# 02_LemonAutopilot_2.net
KiCad netlist of a schematic drawn in Altium Designer
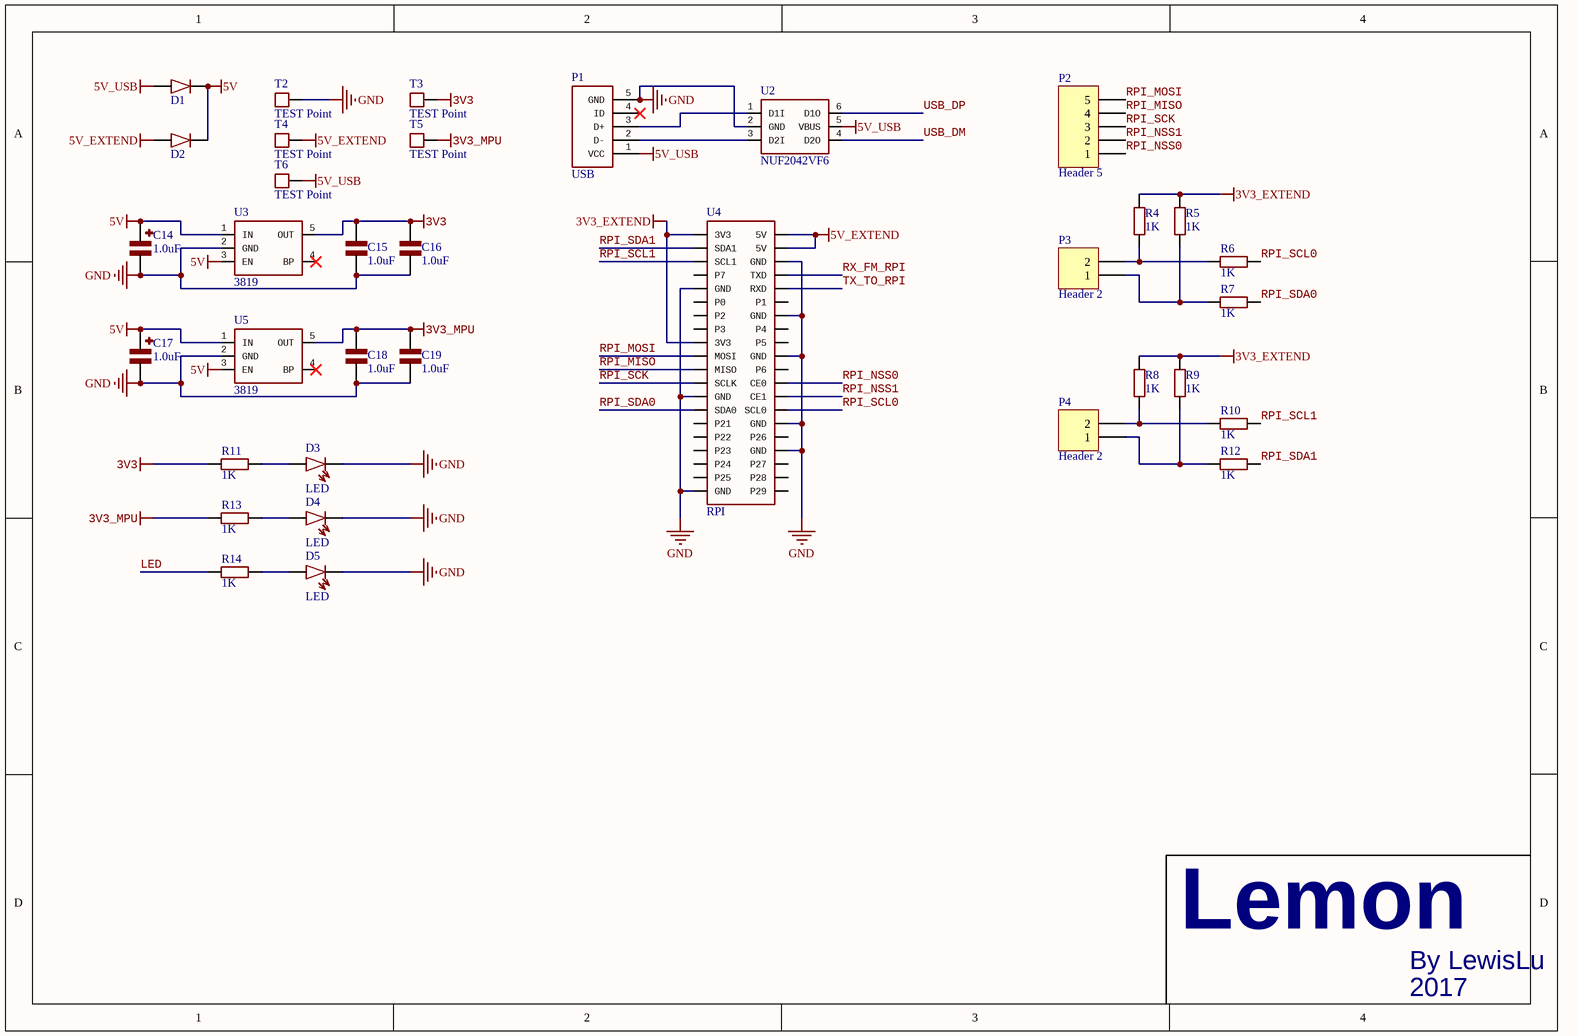
[diagram p0: 02.LemonAutopilot_2.SchDoc]

(export (version "E")
  (design (tool "Eeschema 10.0.6"))
  (components
    (comp (ref "C14") (value "1.0uF") (footprint "3216_C") (libsource (lib "Library") (part "C3216")))
    (comp (ref "C15") (value "1.0uF") (footprint "0603_C") (libsource (lib "Library") (part "C0603")))
    (comp (ref "C16") (value "1.0uF") (footprint "0603_C") (libsource (lib "Library") (part "C0603")))
    (comp (ref "C17") (value "1.0uF") (footprint "3216_C") (libsource (lib "Library") (part "C3216")))
    (comp (ref "C18") (value "1.0uF") (footprint "0603_C") (libsource (lib "Library") (part "C0603")))
    (comp (ref "C19") (value "1.0uF") (footprint "0603_C") (libsource (lib "Library") (part "C0603")))
    (comp (ref "D1") (value "D") (footprint "SOD-323") (libsource (lib "Library") (part "D0603")))
    (comp (ref "D2") (value "D") (footprint "SOD-323") (libsource (lib "Library") (part "D0603")))
    (comp (ref "D3") (value "LED") (footprint "0603_D") (libsource (lib "Library") (part "D0603_LED")))
    (comp (ref "D4") (value "LED") (footprint "0603_D") (libsource (lib "Library") (part "D0603_LED")))
    (comp (ref "D5") (value "LED") (footprint "0603_D") (libsource (lib "Library") (part "D0603_LED")))
    (comp (ref "P1") (value "USB") (footprint "MICROUSB") (libsource (lib "Library") (part "USB")))
    (comp (ref "P2")
      (value "Header 5")
      (footprint "HDR1X5")
      (description "Header, 5-Pin")
      (fields (field (name "PUBLISHER") "Altium Limited"))
      (libsource (lib "Miscellaneous Connectors") (part "Header 5"))
    )
    (comp (ref "P3")
      (value "Header 2")
      (footprint "HDR1X2")
      (description "Header, 2-Pin")
      (fields (field (name "PUBLISHER") "Altium Limited"))
      (libsource (lib "Miscellaneous Connectors") (part "Header 2"))
    )
    (comp (ref "P4")
      (value "Header 2")
      (footprint "HDR1X2")
      (description "Header, 2-Pin")
      (fields (field (name "PUBLISHER") "Altium Limited"))
      (libsource (lib "Miscellaneous Connectors") (part "Header 2"))
    )
    (comp (ref "R4") (value "1K") (footprint "0603_R") (libsource (lib "Library") (part "R0603")))
    (comp (ref "R5") (value "1K") (footprint "0603_R") (libsource (lib "Library") (part "R0603")))
    (comp (ref "R6") (value "1K") (footprint "0603_R") (libsource (lib "") (part "R0603_1")))
    (comp (ref "R7") (value "1K") (footprint "0603_R") (libsource (lib "") (part "R0603_1")))
    (comp (ref "R8") (value "1K") (footprint "0603_R") (libsource (lib "Library") (part "R0603")))
    (comp (ref "R9") (value "1K") (footprint "0603_R") (libsource (lib "Library") (part "R0603")))
    (comp (ref "R10") (value "1K") (footprint "0603_R") (libsource (lib "") (part "R0603_1")))
    (comp (ref "R11") (value "1K") (footprint "0603_R") (libsource (lib "") (part "R0603_1")))
    (comp (ref "R12") (value "1K") (footprint "0603_R") (libsource (lib "") (part "R0603_1")))
    (comp (ref "R13") (value "1K") (footprint "0603_R") (libsource (lib "") (part "R0603_1")))
    (comp (ref "R14") (value "1K") (footprint "0603_R") (libsource (lib "") (part "R0603_1")))
    (comp (ref "T2") (value "TEST Point") (footprint "TEST") (libsource (lib "Library") (part "TEST")))
    (comp (ref "T3") (value "TEST Point") (footprint "TEST") (libsource (lib "Library") (part "TEST")))
    (comp (ref "T4") (value "TEST Point") (footprint "TEST") (libsource (lib "Library") (part "TEST")))
    (comp (ref "T5") (value "TEST Point") (footprint "TEST") (libsource (lib "Library") (part "TEST")))
    (comp (ref "T6") (value "TEST Point") (footprint "TEST") (libsource (lib "Library") (part "TEST")))
    (comp (ref "U2") (value "NUF2042VF6") (libsource (lib "Library") (part "NUF2042XV6")))
    (comp (ref "U3") (value "3819") (footprint "SOT23-5") (libsource (lib "Library") (part "SPX3819")))
    (comp (ref "U4") (value "RPI") (libsource (lib "Library") (part "RPI_EXTEND")))
    (comp (ref "U5") (value "3819") (footprint "SOT23-5") (libsource (lib "Library") (part "SPX3819")))
  )
  (nets
    (net (code "1") (name "/LED") (class "Default")
      (node (ref "R14") (pin "1") (pinfunction "1_1") (pintype "passive"))
    )
    (net (code "2") (name "/RPI_MISO") (class "Default")
      (node (ref "P2") (pin "4") (pinfunction "4_4") (pintype "passive"))
      (node (ref "U4") (pin "21") (pinfunction "MISO_21") (pintype "passive"))
    )
    (net (code "3") (name "/RPI_MOSI") (class "Default")
      (node (ref "P2") (pin "5") (pinfunction "5_5") (pintype "passive"))
      (node (ref "U4") (pin "19") (pinfunction "MOSI_19") (pintype "passive"))
    )
    (net (code "4") (name "/RPI_NSS0") (class "Default")
      (node (ref "P2") (pin "1") (pinfunction "1_1") (pintype "passive"))
      (node (ref "U4") (pin "24") (pinfunction "CE0_24") (pintype "passive"))
    )
    (net (code "5") (name "/RPI_NSS1") (class "Default")
      (node (ref "P2") (pin "2") (pinfunction "2_2") (pintype "passive"))
      (node (ref "U4") (pin "26") (pinfunction "CE1_26") (pintype "passive"))
    )
    (net (code "6") (name "/RPI_SCK") (class "Default")
      (node (ref "P2") (pin "3") (pinfunction "3_3") (pintype "passive"))
      (node (ref "U4") (pin "23") (pinfunction "SCLK_23") (pintype "passive"))
    )
    (net (code "7") (name "/RPI_SCL0") (class "Default")
      (node (ref "R6") (pin "2") (pinfunction "2_2") (pintype "passive"))
      (node (ref "U4") (pin "28") (pinfunction "SCL0_28") (pintype "passive"))
    )
    (net (code "8") (name "/RPI_SCL1") (class "Default")
      (node (ref "R10") (pin "2") (pinfunction "2_2") (pintype "passive"))
      (node (ref "U4") (pin "5") (pinfunction "SCL1_5") (pintype "passive"))
    )
    (net (code "9") (name "/RPI_SDA0") (class "Default")
      (node (ref "R7") (pin "2") (pinfunction "2_2") (pintype "passive"))
      (node (ref "U4") (pin "27") (pinfunction "SDA0_27") (pintype "passive"))
    )
    (net (code "10") (name "/RPI_SDA1") (class "Default")
      (node (ref "R12") (pin "2") (pinfunction "2_2") (pintype "passive"))
      (node (ref "U4") (pin "3") (pinfunction "SDA1_3") (pintype "passive"))
    )
    (net (code "11") (name "/RX_FM_RPI") (class "Default")
      (node (ref "U4") (pin "8") (pinfunction "TXD_8") (pintype "passive"))
    )
    (net (code "12") (name "/TX_TO_RPI") (class "Default")
      (node (ref "U4") (pin "10") (pinfunction "RXD_10") (pintype "passive"))
    )
    (net (code "13") (name "/USB_DM") (class "Default")
      (node (ref "U2") (pin "4") (pinfunction "D2O_4") (pintype "passive"))
    )
    (net (code "14") (name "/USB_DP") (class "Default")
      (node (ref "U2") (pin "6") (pinfunction "D1O_6") (pintype "passive"))
    )
    (net (code "15") (name "3V3") (class "Default")
      (node (ref "C15") (pin "2") (pinfunction "2_2") (pintype "passive"))
      (node (ref "C16") (pin "2") (pinfunction "2_2") (pintype "passive"))
      (node (ref "R11") (pin "1") (pinfunction "1_1") (pintype "passive"))
      (node (ref "T3") (pin "0") (pinfunction "TEST_0") (pintype "passive"))
      (node (ref "U3") (pin "5") (pinfunction "OUT_5") (pintype "passive"))
    )
    (net (code "16") (name "3V3_EXTEND") (class "Default")
      (node (ref "R4") (pin "1") (pinfunction "1_1") (pintype "passive"))
      (node (ref "R5") (pin "1") (pinfunction "1_1") (pintype "passive"))
      (node (ref "R8") (pin "1") (pinfunction "1_1") (pintype "passive"))
      (node (ref "R9") (pin "1") (pinfunction "1_1") (pintype "passive"))
      (node (ref "U4") (pin "1") (pinfunction "3V3_1") (pintype "passive"))
      (node (ref "U4") (pin "17") (pinfunction "3V3_17") (pintype "passive"))
    )
    (net (code "17") (name "3V3_MPU") (class "Default")
      (node (ref "C18") (pin "2") (pinfunction "2_2") (pintype "passive"))
      (node (ref "C19") (pin "2") (pinfunction "2_2") (pintype "passive"))
      (node (ref "R13") (pin "1") (pinfunction "1_1") (pintype "passive"))
      (node (ref "T5") (pin "0") (pinfunction "TEST_0") (pintype "passive"))
      (node (ref "U5") (pin "5") (pinfunction "OUT_5") (pintype "passive"))
    )
    (net (code "18") (name "5V") (class "Default")
      (node (ref "C14") (pin "1") (pinfunction "1_1") (pintype "passive"))
      (node (ref "C17") (pin "1") (pinfunction "1_1") (pintype "passive"))
      (node (ref "D1") (pin "2") (pinfunction "2_2") (pintype "passive"))
      (node (ref "D2") (pin "2") (pinfunction "2_2") (pintype "passive"))
      (node (ref "U3") (pin "1") (pinfunction "IN_1") (pintype "passive"))
      (node (ref "U3") (pin "3") (pinfunction "EN_3") (pintype "passive"))
      (node (ref "U5") (pin "1") (pinfunction "IN_1") (pintype "passive"))
      (node (ref "U5") (pin "3") (pinfunction "EN_3") (pintype "passive"))
    )
    (net (code "19") (name "5V_EXTEND") (class "Default")
      (node (ref "D2") (pin "1") (pinfunction "1_1") (pintype "passive"))
      (node (ref "T4") (pin "0") (pinfunction "TEST_0") (pintype "passive"))
      (node (ref "U4") (pin "2") (pinfunction "5V_2") (pintype "passive"))
      (node (ref "U4") (pin "4") (pinfunction "5V_4") (pintype "passive"))
    )
    (net (code "20") (name "5V_USB") (class "Default")
      (node (ref "D1") (pin "1") (pinfunction "1_1") (pintype "passive"))
      (node (ref "P1") (pin "1") (pinfunction "VCC_1") (pintype "passive"))
      (node (ref "T6") (pin "0") (pinfunction "TEST_0") (pintype "passive"))
      (node (ref "U2") (pin "5") (pinfunction "VBUS_5") (pintype "passive"))
    )
    (net (code "21") (name "GND") (class "Default")
      (node (ref "C14") (pin "2") (pinfunction "2_2") (pintype "passive"))
      (node (ref "C15") (pin "1") (pinfunction "1_1") (pintype "passive"))
      (node (ref "C16") (pin "1") (pinfunction "1_1") (pintype "passive"))
      (node (ref "C17") (pin "2") (pinfunction "2_2") (pintype "passive"))
      (node (ref "C18") (pin "1") (pinfunction "1_1") (pintype "passive"))
      (node (ref "C19") (pin "1") (pinfunction "1_1") (pintype "passive"))
      (node (ref "D3") (pin "2") (pinfunction "2_2") (pintype "passive"))
      (node (ref "D4") (pin "2") (pinfunction "2_2") (pintype "passive"))
      (node (ref "D5") (pin "2") (pinfunction "2_2") (pintype "passive"))
      (node (ref "P1") (pin "5") (pinfunction "GND_5") (pintype "passive"))
      (node (ref "T2") (pin "0") (pinfunction "TEST_0") (pintype "passive"))
      (node (ref "U2") (pin "2") (pinfunction "GND_2") (pintype "passive"))
      (node (ref "U3") (pin "2") (pinfunction "GND_2") (pintype "passive"))
      (node (ref "U4") (pin "14") (pinfunction "GND_14") (pintype "passive"))
      (node (ref "U4") (pin "20") (pinfunction "GND_20") (pintype "passive"))
      (node (ref "U4") (pin "25") (pinfunction "GND_25") (pintype "passive"))
      (node (ref "U4") (pin "30") (pinfunction "GND_30") (pintype "passive"))
      (node (ref "U4") (pin "34") (pinfunction "GND_34") (pintype "passive"))
      (node (ref "U4") (pin "39") (pinfunction "GND_39") (pintype "passive"))
      (node (ref "U4") (pin "6") (pinfunction "GND_6") (pintype "passive"))
      (node (ref "U4") (pin "9") (pinfunction "GND_9") (pintype "passive"))
      (node (ref "U5") (pin "2") (pinfunction "GND_2") (pintype "passive"))
    )
    (net (code "22") (name "Net-(D3-Pad1)") (class "Default")
      (node (ref "D3") (pin "1") (pinfunction "1_1") (pintype "passive"))
      (node (ref "R11") (pin "2") (pinfunction "2_2") (pintype "passive"))
    )
    (net (code "23") (name "Net-(D4-Pad1)") (class "Default")
      (node (ref "D4") (pin "1") (pinfunction "1_1") (pintype "passive"))
      (node (ref "R13") (pin "2") (pinfunction "2_2") (pintype "passive"))
    )
    (net (code "24") (name "Net-(D5-Pad1)") (class "Default")
      (node (ref "D5") (pin "1") (pinfunction "1_1") (pintype "passive"))
      (node (ref "R14") (pin "2") (pinfunction "2_2") (pintype "passive"))
    )
    (net (code "25") (name "Net-(P1-D+)") (class "Default")
      (node (ref "P1") (pin "3") (pinfunction "D+_3") (pintype "passive"))
      (node (ref "U2") (pin "1") (pinfunction "D1I_1") (pintype "passive"))
    )
    (net (code "26") (name "Net-(P1-D-)") (class "Default")
      (node (ref "P1") (pin "2") (pinfunction "D-_2") (pintype "passive"))
      (node (ref "U2") (pin "3") (pinfunction "D2I_3") (pintype "passive"))
    )
    (net (code "27") (name "Net-(P3-Pad1)") (class "Default")
      (node (ref "P3") (pin "1") (pinfunction "1_1") (pintype "passive"))
      (node (ref "R5") (pin "2") (pinfunction "2_2") (pintype "passive"))
      (node (ref "R7") (pin "1") (pinfunction "1_1") (pintype "passive"))
    )
    (net (code "28") (name "Net-(P3-Pad2)") (class "Default")
      (node (ref "P3") (pin "2") (pinfunction "2_2") (pintype "passive"))
      (node (ref "R4") (pin "2") (pinfunction "2_2") (pintype "passive"))
      (node (ref "R6") (pin "1") (pinfunction "1_1") (pintype "passive"))
    )
    (net (code "29") (name "Net-(P4-Pad1)") (class "Default")
      (node (ref "P4") (pin "1") (pinfunction "1_1") (pintype "passive"))
      (node (ref "R12") (pin "1") (pinfunction "1_1") (pintype "passive"))
      (node (ref "R9") (pin "2") (pinfunction "2_2") (pintype "passive"))
    )
    (net (code "30") (name "Net-(P4-Pad2)") (class "Default")
      (node (ref "P4") (pin "2") (pinfunction "2_2") (pintype "passive"))
      (node (ref "R10") (pin "1") (pinfunction "1_1") (pintype "passive"))
      (node (ref "R8") (pin "2") (pinfunction "2_2") (pintype "passive"))
    )
    (net (code "31") (name "unconnected-(P1-ID-Pad4)") (class "Default")
      (node (ref "P1") (pin "4") (pinfunction "ID_4") (pintype "passive+no_connect"))
    )
    (net (code "32") (name "unconnected-(U3-BP-Pad4)") (class "Default")
      (node (ref "U3") (pin "4") (pinfunction "BP_4") (pintype "passive+no_connect"))
    )
    (net (code "33") (name "unconnected-(U4-P0-Pad11)") (class "Default")
      (node (ref "U4") (pin "11") (pinfunction "P0_11") (pintype "passive"))
    )
    (net (code "34") (name "unconnected-(U4-P1-Pad12)") (class "Default")
      (node (ref "U4") (pin "12") (pinfunction "P1_12") (pintype "passive"))
    )
    (net (code "35") (name "unconnected-(U4-P2-Pad13)") (class "Default")
      (node (ref "U4") (pin "13") (pinfunction "P2_13") (pintype "passive"))
    )
    (net (code "36") (name "unconnected-(U4-P3-Pad15)") (class "Default")
      (node (ref "U4") (pin "15") (pinfunction "P3_15") (pintype "passive"))
    )
    (net (code "37") (name "unconnected-(U4-P4-Pad16)") (class "Default")
      (node (ref "U4") (pin "16") (pinfunction "P4_16") (pintype "passive"))
    )
    (net (code "38") (name "unconnected-(U4-P5-Pad18)") (class "Default")
      (node (ref "U4") (pin "18") (pinfunction "P5_18") (pintype "passive"))
    )
    (net (code "39") (name "unconnected-(U4-P6-Pad22)") (class "Default")
      (node (ref "U4") (pin "22") (pinfunction "P6_22") (pintype "passive"))
    )
    (net (code "40") (name "unconnected-(U4-P7-Pad7)") (class "Default")
      (node (ref "U4") (pin "7") (pinfunction "P7_7") (pintype "passive"))
    )
    (net (code "41") (name "unconnected-(U4-P21-Pad29)") (class "Default")
      (node (ref "U4") (pin "29") (pinfunction "P21_29") (pintype "passive"))
    )
    (net (code "42") (name "unconnected-(U4-P22-Pad31)") (class "Default")
      (node (ref "U4") (pin "31") (pinfunction "P22_31") (pintype "passive"))
    )
    (net (code "43") (name "unconnected-(U4-P23-Pad33)") (class "Default")
      (node (ref "U4") (pin "33") (pinfunction "P23_33") (pintype "passive"))
    )
    (net (code "44") (name "unconnected-(U4-P24-Pad35)") (class "Default")
      (node (ref "U4") (pin "35") (pinfunction "P24_35") (pintype "passive"))
    )
    (net (code "45") (name "unconnected-(U4-P25-Pad37)") (class "Default")
      (node (ref "U4") (pin "37") (pinfunction "P25_37") (pintype "passive"))
    )
    (net (code "46") (name "unconnected-(U4-P26-Pad32)") (class "Default")
      (node (ref "U4") (pin "32") (pinfunction "P26_32") (pintype "passive"))
    )
    (net (code "47") (name "unconnected-(U4-P27-Pad36)") (class "Default")
      (node (ref "U4") (pin "36") (pinfunction "P27_36") (pintype "passive"))
    )
    (net (code "48") (name "unconnected-(U4-P28-Pad38)") (class "Default")
      (node (ref "U4") (pin "38") (pinfunction "P28_38") (pintype "passive"))
    )
    (net (code "49") (name "unconnected-(U4-P29-Pad40)") (class "Default")
      (node (ref "U4") (pin "40") (pinfunction "P29_40") (pintype "passive"))
    )
    (net (code "50") (name "unconnected-(U5-BP-Pad4)") (class "Default")
      (node (ref "U5") (pin "4") (pinfunction "BP_4") (pintype "passive+no_connect"))
    )
  )
)
